# KieserTrainer.net
KiCad netlist of a schematic drawn in EAGLE
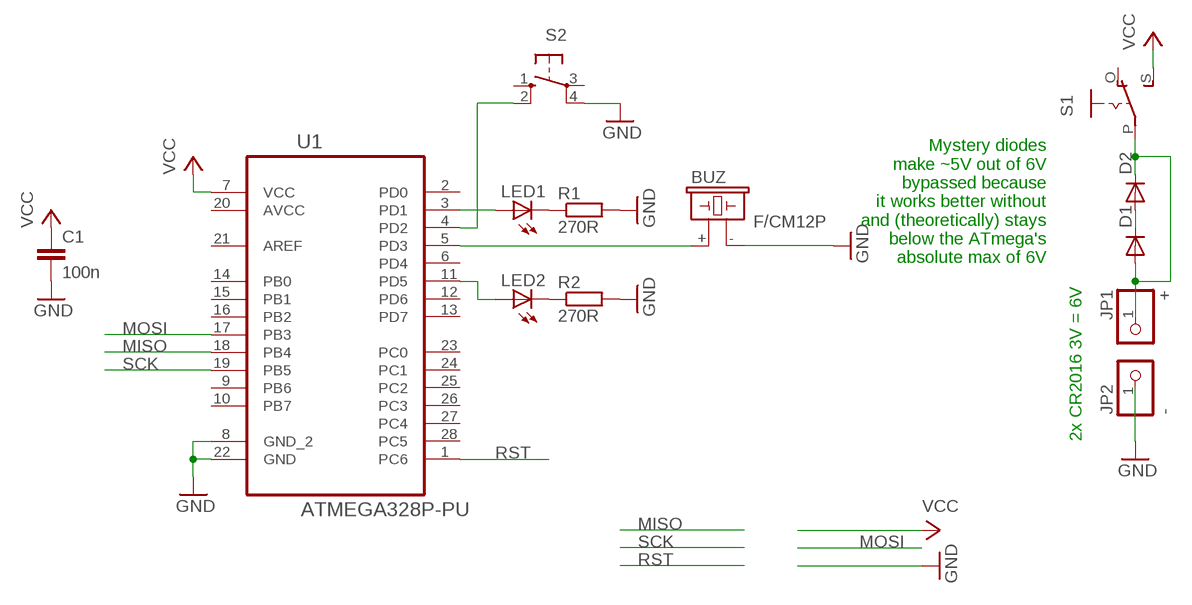
[diagram p0: schematic, sheet 1]

(export (version "E")
  (design (tool "Eeschema 10.0.6"))
  (components
    (comp (ref "BUZ")
      (value "F/CM12P")
      (footprint "eagle-import:F_CM12P")
      (libsource (lib "eagle-import") (part "F/CM12P"))
    )
    (comp (ref "C1")
      (value "100n")
      (footprint "eagle-import:C0805")
      (libsource (lib "eagle-import") (part "C-EUC0805"))
    )
    (comp (ref "D1")
      (value "DIODE-D-7.5")
      (footprint "eagle-import:D-7.5")
      (libsource (lib "eagle-import") (part "DIODE-D-7.5"))
    )
    (comp (ref "D2")
      (value "DIODE-D-7.5")
      (footprint "eagle-import:D-7.5")
      (libsource (lib "eagle-import") (part "DIODE-D-7.5"))
    )
    (comp (ref "JP1")
      (value "+")
      (footprint "eagle-import:1X01")
      (libsource (lib "eagle-import") (part "PINHD-1X1"))
    )
    (comp (ref "JP2")
      (value "-")
      (footprint "eagle-import:1X01")
      (libsource (lib "eagle-import") (part "PINHD-1X1"))
    )
    (comp (ref "LED1")
      (value "LED3MM")
      (footprint "eagle-import:LED3MM")
      (libsource (lib "eagle-import") (part "LED3MM"))
    )
    (comp (ref "LED2")
      (value "LED3MM")
      (footprint "eagle-import:LED3MM")
      (libsource (lib "eagle-import") (part "LED3MM"))
    )
    (comp (ref "R1")
      (value "270R")
      (footprint "eagle-import:R0805")
      (libsource (lib "eagle-import") (part "R-EU_R0805"))
    )
    (comp (ref "R2")
      (value "270R")
      (footprint "eagle-import:R0805")
      (libsource (lib "eagle-import") (part "R-EU_R0805"))
    )
    (comp (ref "S1")
      (value "EG1218S")
      (footprint "eagle-import:EG1218")
      (libsource (lib "eagle-import") (part "EG1218S"))
    )
    (comp (ref "S2")
      (value "10-XX")
      (footprint "eagle-import:B3F-10XX")
      (fields (field (name "MPN") "B3F-1000"))
      (libsource (lib "eagle-import") (part "10-XX"))
    )
    (comp (ref "U1")
      (value "ATMEGA328P-PU")
      (footprint "eagle-import:DIP254P762X457-28")
      (libsource (lib "eagle-import") (part "ATMEGA328P-PU"))
    )
  )
  (nets
    (net (code "1") (name "/AVCC") (class "Default")
      (node (ref "U1") (pin "20") (pinfunction "AVCC_20") (pintype "power_in"))
    )
    (net (code "2") (name "/MISO") (class "Default")
      (node (ref "U1") (pin "18") (pinfunction "PB4_18") (pintype "bidirectional"))
    )
    (net (code "3") (name "/MOSI") (class "Default")
      (node (ref "U1") (pin "17") (pinfunction "PB3_17") (pintype "bidirectional"))
    )
    (net (code "4") (name "/RST") (class "Default")
      (node (ref "U1") (pin "1") (pinfunction "PC6_1") (pintype "bidirectional"))
    )
    (net (code "5") (name "/SCK") (class "Default")
      (node (ref "U1") (pin "19") (pinfunction "PB5_19") (pintype "bidirectional"))
    )
    (net (code "6") (name "GND") (class "Default")
      (node (ref "BUZ") (pin "-") (pinfunction "2_-") (pintype "passive"))
      (node (ref "C1") (pin "2") (pinfunction "2_2") (pintype "passive"))
      (node (ref "JP2") (pin "1") (pinfunction "1_1") (pintype "passive"))
      (node (ref "R1") (pin "2") (pinfunction "2_2") (pintype "passive"))
      (node (ref "R2") (pin "2") (pinfunction "2_2") (pintype "passive"))
      (node (ref "S2") (pin "4") (pinfunction "P1_4") (pintype "passive"))
      (node (ref "U1") (pin "22") (pinfunction "GND_22") (pintype "passive"))
      (node (ref "U1") (pin "8") (pinfunction "GND_2_8") (pintype "passive"))
    )
    (net (code "7") (name "Net-(BUZ-1)") (class "Default")
      (node (ref "BUZ") (pin "+") (pinfunction "1_+") (pintype "passive"))
      (node (ref "U1") (pin "5") (pinfunction "PD3_5") (pintype "bidirectional"))
    )
    (net (code "8") (name "Net-(D1-PadA)") (class "Default")
      (node (ref "D1") (pin "A") (pinfunction "A_A") (pintype "passive"))
      (node (ref "D2") (pin "C") (pinfunction "C_C") (pintype "passive"))
      (node (ref "JP1") (pin "1") (pinfunction "1_1") (pintype "passive"))
      (node (ref "S1") (pin "P") (pinfunction "P_P") (pintype "passive"))
    )
    (net (code "9") (name "Net-(D1-PadC)") (class "Default")
      (node (ref "D1") (pin "C") (pinfunction "C_C") (pintype "passive"))
      (node (ref "D2") (pin "A") (pinfunction "A_A") (pintype "passive"))
    )
    (net (code "10") (name "Net-(LED1-C)") (class "Default")
      (node (ref "LED1") (pin "K") (pinfunction "C_K") (pintype "passive"))
      (node (ref "R1") (pin "1") (pinfunction "1_1") (pintype "passive"))
    )
    (net (code "11") (name "Net-(LED2-C)") (class "Default")
      (node (ref "LED2") (pin "K") (pinfunction "C_K") (pintype "passive"))
      (node (ref "R2") (pin "1") (pinfunction "1_1") (pintype "passive"))
    )
    (net (code "12") (name "Net-(S2-S1)") (class "Default")
      (node (ref "S2") (pin "2") (pinfunction "S1_2") (pintype "passive"))
      (node (ref "U1") (pin "4") (pinfunction "PD2_4") (pintype "bidirectional"))
    )
    (net (code "13") (name "Net-(U1-PD1)") (class "Default")
      (node (ref "LED1") (pin "A") (pinfunction "A_A") (pintype "passive"))
      (node (ref "U1") (pin "3") (pinfunction "PD1_3") (pintype "bidirectional"))
    )
    (net (code "14") (name "Net-(U1-PD5)") (class "Default")
      (node (ref "LED2") (pin "A") (pinfunction "A_A") (pintype "passive"))
      (node (ref "U1") (pin "11") (pinfunction "PD5_11") (pintype "bidirectional"))
    )
    (net (code "15") (name "VCC") (class "Default")
      (node (ref "C1") (pin "1") (pinfunction "1_1") (pintype "passive"))
      (node (ref "S1") (pin "S") (pinfunction "S_S") (pintype "passive"))
      (node (ref "U1") (pin "7") (pinfunction "VCC_7") (pintype "power_in"))
    )
    (net (code "16") (name "unconnected-(S1-PadO)") (class "Default")
      (node (ref "S1") (pin "O") (pinfunction "O_O") (pintype "passive"))
    )
    (net (code "17") (name "unconnected-(S2-P-Pad3)") (class "Default")
      (node (ref "S2") (pin "3") (pinfunction "P_3") (pintype "passive"))
    )
    (net (code "18") (name "unconnected-(S2-S-Pad1)") (class "Default")
      (node (ref "S2") (pin "1") (pinfunction "S_1") (pintype "passive"))
    )
    (net (code "19") (name "unconnected-(U1-AREF-Pad21)") (class "Default")
      (node (ref "U1") (pin "21") (pinfunction "AREF_21") (pintype "input"))
    )
    (net (code "20") (name "unconnected-(U1-PB0-Pad14)") (class "Default")
      (node (ref "U1") (pin "14") (pinfunction "PB0_14") (pintype "bidirectional"))
    )
    (net (code "21") (name "unconnected-(U1-PB1-Pad15)") (class "Default")
      (node (ref "U1") (pin "15") (pinfunction "PB1_15") (pintype "bidirectional"))
    )
    (net (code "22") (name "unconnected-(U1-PB2-Pad16)") (class "Default")
      (node (ref "U1") (pin "16") (pinfunction "PB2_16") (pintype "bidirectional"))
    )
    (net (code "23") (name "unconnected-(U1-PB6-Pad9)") (class "Default")
      (node (ref "U1") (pin "9") (pinfunction "PB6_9") (pintype "bidirectional"))
    )
    (net (code "24") (name "unconnected-(U1-PB7-Pad10)") (class "Default")
      (node (ref "U1") (pin "10") (pinfunction "PB7_10") (pintype "bidirectional"))
    )
    (net (code "25") (name "unconnected-(U1-PC0-Pad23)") (class "Default")
      (node (ref "U1") (pin "23") (pinfunction "PC0_23") (pintype "bidirectional"))
    )
    (net (code "26") (name "unconnected-(U1-PC1-Pad24)") (class "Default")
      (node (ref "U1") (pin "24") (pinfunction "PC1_24") (pintype "bidirectional"))
    )
    (net (code "27") (name "unconnected-(U1-PC2-Pad25)") (class "Default")
      (node (ref "U1") (pin "25") (pinfunction "PC2_25") (pintype "bidirectional"))
    )
    (net (code "28") (name "unconnected-(U1-PC3-Pad26)") (class "Default")
      (node (ref "U1") (pin "26") (pinfunction "PC3_26") (pintype "bidirectional"))
    )
    (net (code "29") (name "unconnected-(U1-PC4-Pad27)") (class "Default")
      (node (ref "U1") (pin "27") (pinfunction "PC4_27") (pintype "bidirectional"))
    )
    (net (code "30") (name "unconnected-(U1-PC5-Pad28)") (class "Default")
      (node (ref "U1") (pin "28") (pinfunction "PC5_28") (pintype "bidirectional"))
    )
    (net (code "31") (name "unconnected-(U1-PD0-Pad2)") (class "Default")
      (node (ref "U1") (pin "2") (pinfunction "PD0_2") (pintype "bidirectional"))
    )
    (net (code "32") (name "unconnected-(U1-PD4-Pad6)") (class "Default")
      (node (ref "U1") (pin "6") (pinfunction "PD4_6") (pintype "bidirectional"))
    )
    (net (code "33") (name "unconnected-(U1-PD6-Pad12)") (class "Default")
      (node (ref "U1") (pin "12") (pinfunction "PD6_12") (pintype "bidirectional"))
    )
    (net (code "34") (name "unconnected-(U1-PD7-Pad13)") (class "Default")
      (node (ref "U1") (pin "13") (pinfunction "PD7_13") (pintype "bidirectional"))
    )
  )
)
